# Connectors-SD.net
KiCad netlist of a schematic drawn in Altium Designer
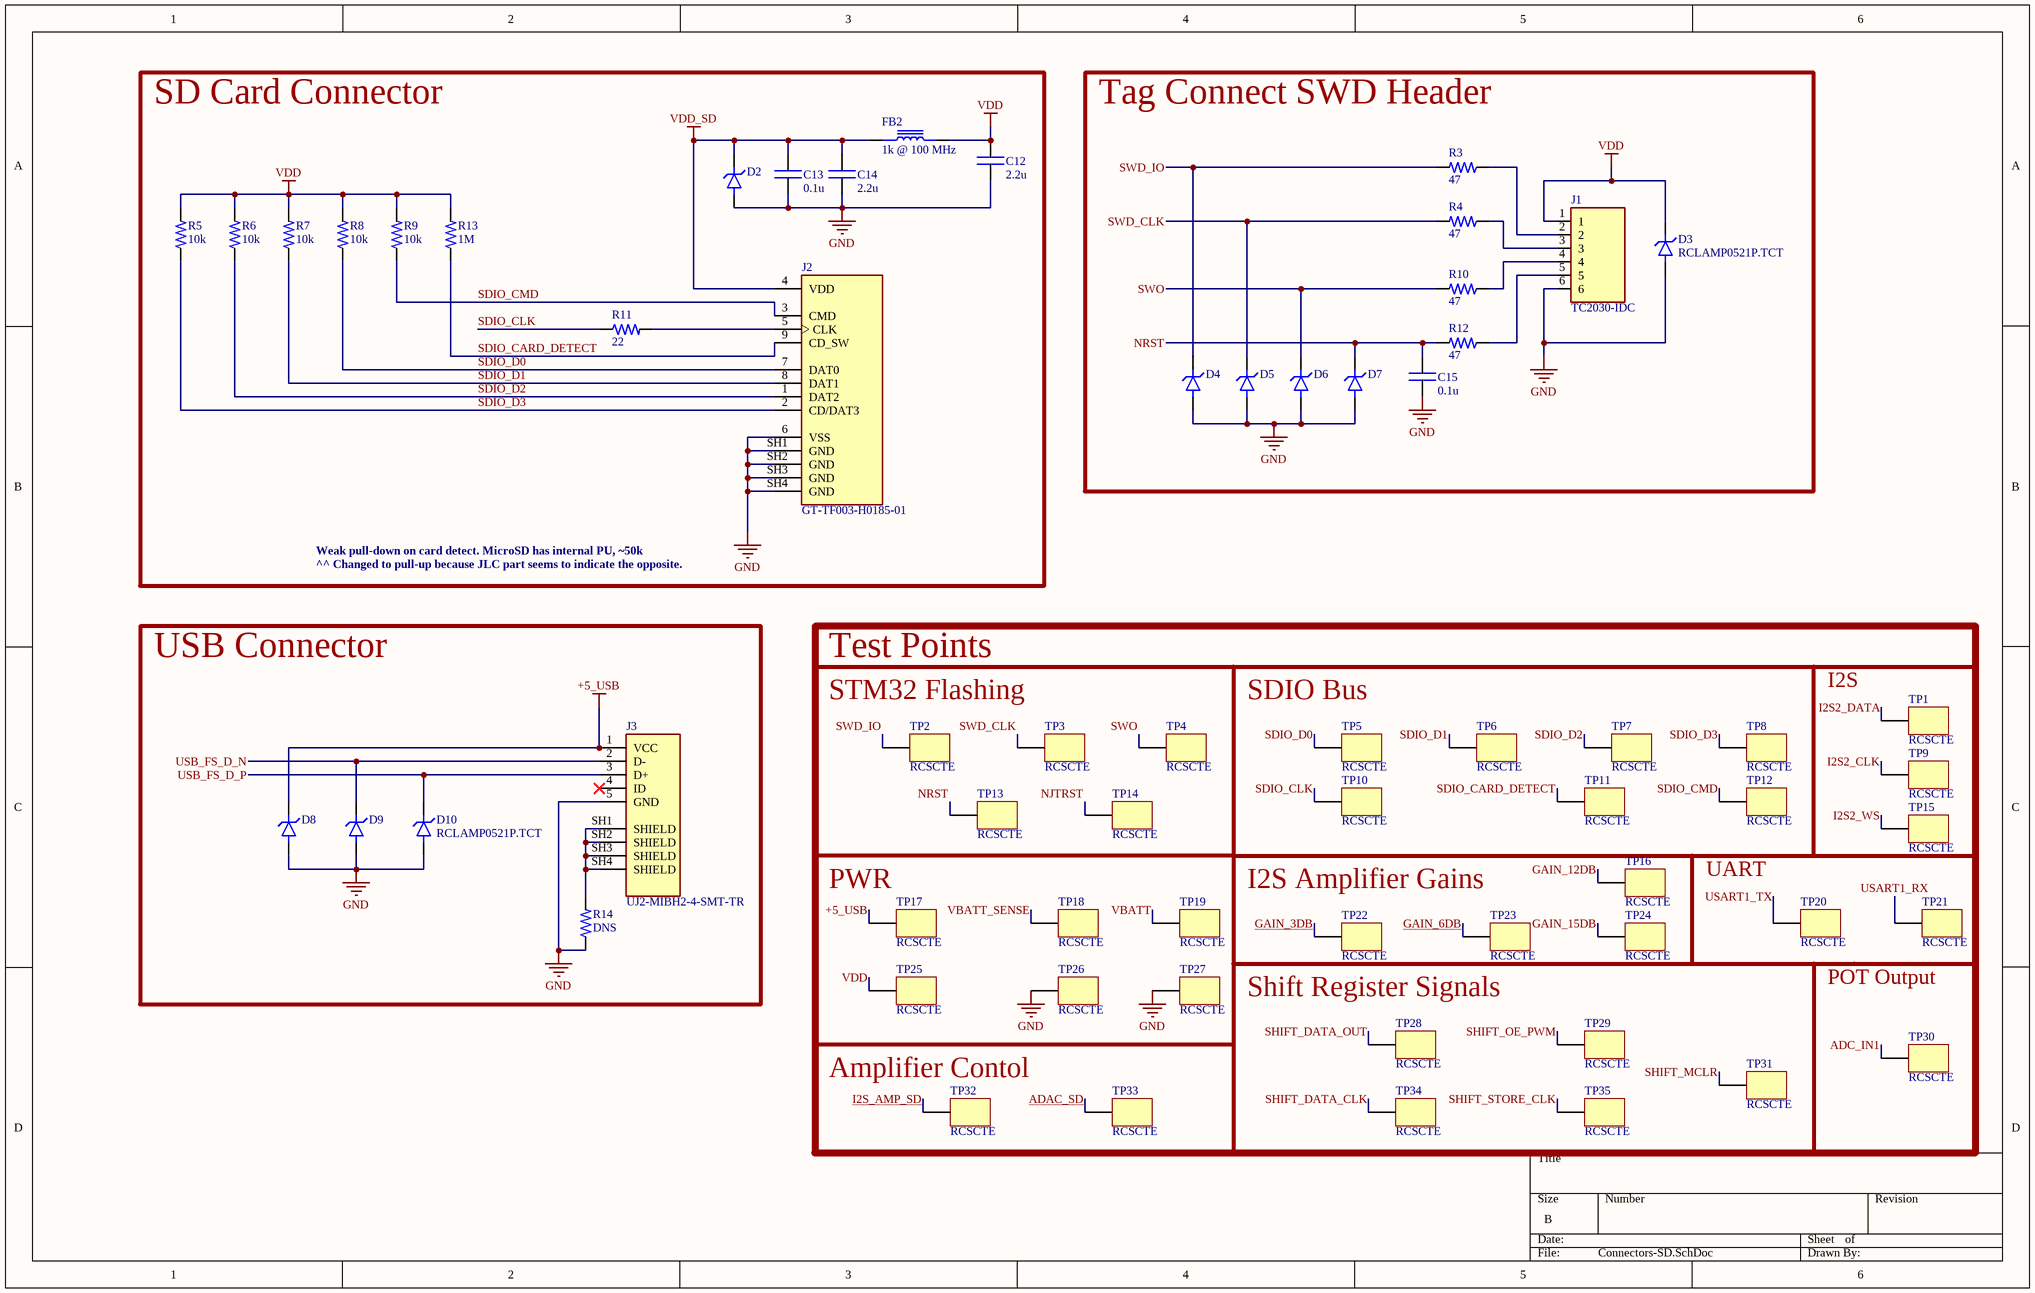
[diagram p0: Connectors-SD.SchDoc]

(export (version "E")
  (design (tool "Eeschema 10.0.6"))
  (components
    (comp (ref "C12")
      (value "2.2u")
      (footprint "Christmas-2023_Soundboard:0603-CAP")
      (description "Capaicitor")
      (fields (field (name "Comment") "CAP"))
      (libsource (lib "Christmas-2023_Soundboard") (part "CAP"))
    )
    (comp (ref "C13")
      (value "0.1u")
      (footprint "Christmas-2023_Soundboard:0603-CAP")
      (description "Capaicitor")
      (fields (field (name "Comment") "CAP"))
      (libsource (lib "Christmas-2023_Soundboard") (part "CAP"))
    )
    (comp (ref "C14")
      (value "2.2u")
      (footprint "Christmas-2023_Soundboard:0603-CAP")
      (description "Capaicitor")
      (fields (field (name "Comment") "CAP"))
      (libsource (lib "Christmas-2023_Soundboard") (part "CAP"))
    )
    (comp (ref "C15")
      (value "0.1u")
      (footprint "Christmas-2023_Soundboard:0603-CAP")
      (description "Capaicitor")
      (fields (field (name "Comment") "CAP"))
      (libsource (lib "Christmas-2023_Soundboard") (part "CAP"))
    )
    (comp (ref "D2")
      (value "RCLAMP0521P.TCT")
      (footprint "Christmas-2023_Soundboard:RCLAMP0521P.TCT")
      (description "25V Clamp 4A (8/20µs) Ipp Tvs Diode Surface Mount SLP1006P2")
      (fields (field (name "MFR") "Semtech Corporation"))
      (libsource (lib "Christmas-2023_Soundboard") (part "TVS DIODE"))
    )
    (comp (ref "D3")
      (value "RCLAMP0521P.TCT")
      (footprint "Christmas-2023_Soundboard:RCLAMP0521P.TCT")
      (description "25V Clamp 4A (8/20µs) Ipp Tvs Diode Surface Mount SLP1006P2")
      (fields (field (name "MFR") "Semtech Corporation"))
      (libsource (lib "Christmas-2023_Soundboard") (part "TVS DIODE"))
    )
    (comp (ref "D4")
      (value "RCLAMP0521P.TCT")
      (footprint "Christmas-2023_Soundboard:RCLAMP0521P.TCT")
      (description "25V Clamp 4A (8/20µs) Ipp Tvs Diode Surface Mount SLP1006P2")
      (fields (field (name "MFR") "Semtech Corporation"))
      (libsource (lib "Christmas-2023_Soundboard") (part "TVS DIODE"))
    )
    (comp (ref "D5")
      (value "RCLAMP0521P.TCT")
      (footprint "Christmas-2023_Soundboard:RCLAMP0521P.TCT")
      (description "25V Clamp 4A (8/20µs) Ipp Tvs Diode Surface Mount SLP1006P2")
      (fields (field (name "MFR") "Semtech Corporation"))
      (libsource (lib "Christmas-2023_Soundboard") (part "TVS DIODE"))
    )
    (comp (ref "D6")
      (value "RCLAMP0521P.TCT")
      (footprint "Christmas-2023_Soundboard:RCLAMP0521P.TCT")
      (description "25V Clamp 4A (8/20µs) Ipp Tvs Diode Surface Mount SLP1006P2")
      (fields (field (name "MFR") "Semtech Corporation"))
      (libsource (lib "Christmas-2023_Soundboard") (part "TVS DIODE"))
    )
    (comp (ref "D7")
      (value "RCLAMP0521P.TCT")
      (footprint "Christmas-2023_Soundboard:RCLAMP0521P.TCT")
      (description "25V Clamp 4A (8/20µs) Ipp Tvs Diode Surface Mount SLP1006P2")
      (fields (field (name "MFR") "Semtech Corporation"))
      (libsource (lib "Christmas-2023_Soundboard") (part "TVS DIODE"))
    )
    (comp (ref "D8")
      (value "RCLAMP0521P.TCT")
      (footprint "Christmas-2023_Soundboard:RCLAMP0521P.TCT")
      (description "25V Clamp 4A (8/20µs) Ipp Tvs Diode Surface Mount SLP1006P2")
      (fields (field (name "MFR") "Semtech Corporation"))
      (libsource (lib "Christmas-2023_Soundboard") (part "TVS DIODE"))
    )
    (comp (ref "D9")
      (value "RCLAMP0521P.TCT")
      (footprint "Christmas-2023_Soundboard:RCLAMP0521P.TCT")
      (description "25V Clamp 4A (8/20µs) Ipp Tvs Diode Surface Mount SLP1006P2")
      (fields (field (name "MFR") "Semtech Corporation"))
      (libsource (lib "Christmas-2023_Soundboard") (part "TVS DIODE"))
    )
    (comp (ref "D10")
      (value "RCLAMP0521P.TCT")
      (footprint "Christmas-2023_Soundboard:RCLAMP0521P.TCT")
      (description "25V Clamp 4A (8/20µs) Ipp Tvs Diode Surface Mount SLP1006P2")
      (fields (field (name "MFR") "Semtech Corporation"))
      (libsource (lib "Christmas-2023_Soundboard") (part "TVS DIODE"))
    )
    (comp (ref "FB2")
      (value "1k @ 100 MHz")
      (footprint "Christmas-2023_Soundboard:0603-FB")
      (fields (field (name "MFR") "TDK"))
      (libsource (lib "Christmas-2023_Soundboard") (part "FERRITE BEAD"))
    )
    (comp (ref "J1")
      (value "TC2030-IDC")
      (footprint "Christmas-2023_Soundboard:TAG CONNECT TC2030IDC - NO 3D MODEL")
      (description "\"Plug of Nails\" POGO Pin connector")
      (fields (field (name "MFR") "Tag-Connect"))
      (libsource (lib "Christmas-2023_Soundboard") (part "TAG CONNECT POGO HEADER"))
    )
    (comp (ref "J2")
      (value "GT-TF003-H0185-01")
      (footprint "Christmas-2023_Soundboard:GTTF003H018501")
      (fields (field (name "MFR") "G-Switch"))
      (libsource (lib "Christmas-2023_Soundboard") (part "SD-CONN-SMD_JLC"))
    )
    (comp (ref "J3")
      (value "UJ2-MIBH2-4-SMT-TR")
      (footprint "Christmas-2023_Soundboard:USB MICRO JLC")
      (description "Micro B, USB 2.0, 1.8 A, Right Angle, Surface Mount (SMT), USB Receptacle")
      (fields (field (name "MFR") "D-CHAIN"))
      (libsource (lib "Christmas-2023_Soundboard") (part "Micro USB Port"))
    )
    (comp (ref "R3")
      (value "47")
      (footprint "Christmas-2023_Soundboard:0603-RES")
      (description "Resistor")
      (fields (field (name "Comment") "RES"))
      (libsource (lib "Christmas-2023_Soundboard") (part "RES"))
    )
    (comp (ref "R4")
      (value "47")
      (footprint "Christmas-2023_Soundboard:0603-RES")
      (description "Resistor")
      (fields (field (name "Comment") "RES"))
      (libsource (lib "Christmas-2023_Soundboard") (part "RES"))
    )
    (comp (ref "R5")
      (value "10k")
      (footprint "Christmas-2023_Soundboard:0603-RES")
      (description "Resistor")
      (fields (field (name "Comment") "RES"))
      (libsource (lib "Christmas-2023_Soundboard") (part "RES"))
    )
    (comp (ref "R6")
      (value "10k")
      (footprint "Christmas-2023_Soundboard:0603-RES")
      (description "Resistor")
      (fields (field (name "Comment") "RES"))
      (libsource (lib "Christmas-2023_Soundboard") (part "RES"))
    )
    (comp (ref "R7")
      (value "10k")
      (footprint "Christmas-2023_Soundboard:0603-RES")
      (description "Resistor")
      (fields (field (name "Comment") "RES"))
      (libsource (lib "Christmas-2023_Soundboard") (part "RES"))
    )
    (comp (ref "R8")
      (value "10k")
      (footprint "Christmas-2023_Soundboard:0603-RES")
      (description "Resistor")
      (fields (field (name "Comment") "RES"))
      (libsource (lib "Christmas-2023_Soundboard") (part "RES"))
    )
    (comp (ref "R9")
      (value "10k")
      (footprint "Christmas-2023_Soundboard:0603-RES")
      (description "Resistor")
      (fields (field (name "Comment") "RES"))
      (libsource (lib "Christmas-2023_Soundboard") (part "RES"))
    )
    (comp (ref "R10")
      (value "47")
      (footprint "Christmas-2023_Soundboard:0603-RES")
      (description "Resistor")
      (fields (field (name "Comment") "RES"))
      (libsource (lib "Christmas-2023_Soundboard") (part "RES"))
    )
    (comp (ref "R11")
      (value "22")
      (footprint "Christmas-2023_Soundboard:0603-RES")
      (description "Resistor")
      (fields (field (name "Comment") "RES"))
      (libsource (lib "Christmas-2023_Soundboard") (part "RES"))
    )
    (comp (ref "R12")
      (value "47")
      (footprint "Christmas-2023_Soundboard:0603-RES")
      (description "Resistor")
      (fields (field (name "Comment") "RES"))
      (libsource (lib "Christmas-2023_Soundboard") (part "RES"))
    )
    (comp (ref "R13")
      (value "1M")
      (footprint "Christmas-2023_Soundboard:0603-RES")
      (description "Resistor")
      (fields (field (name "Comment") "RES"))
      (libsource (lib "Christmas-2023_Soundboard") (part "RES"))
    )
    (comp (ref "R14")
      (value "DNS")
      (footprint "Christmas-2023_Soundboard:0603-RES")
      (description "Resistor")
      (fields (field (name "Comment") "RES"))
      (libsource (lib "Christmas-2023_Soundboard") (part "RES"))
    )
    (comp (ref "TP1")
      (value "RCSCTE")
      (footprint "Christmas-2023_Soundboard:RCWCTE")
      (description "Test Point, Surface Mount")
      (fields (field (name "MFR") "KOA Speer Electronics, Inc."))
      (libsource (lib "Christmas-2023_Soundboard") (part "Test Point"))
    )
    (comp (ref "TP2")
      (value "RCSCTE")
      (footprint "Christmas-2023_Soundboard:RCWCTE")
      (description "Test Point, Surface Mount")
      (fields (field (name "MFR") "KOA Speer Electronics, Inc."))
      (libsource (lib "Christmas-2023_Soundboard") (part "Test Point"))
    )
    (comp (ref "TP3")
      (value "RCSCTE")
      (footprint "Christmas-2023_Soundboard:RCWCTE")
      (description "Test Point, Surface Mount")
      (fields (field (name "MFR") "KOA Speer Electronics, Inc."))
      (libsource (lib "Christmas-2023_Soundboard") (part "Test Point"))
    )
    (comp (ref "TP4")
      (value "RCSCTE")
      (footprint "Christmas-2023_Soundboard:RCWCTE")
      (description "Test Point, Surface Mount")
      (fields (field (name "MFR") "KOA Speer Electronics, Inc."))
      (libsource (lib "Christmas-2023_Soundboard") (part "Test Point"))
    )
    (comp (ref "TP5")
      (value "RCSCTE")
      (footprint "Christmas-2023_Soundboard:RCWCTE")
      (description "Test Point, Surface Mount")
      (fields (field (name "MFR") "KOA Speer Electronics, Inc."))
      (libsource (lib "Christmas-2023_Soundboard") (part "Test Point"))
    )
    (comp (ref "TP6")
      (value "RCSCTE")
      (footprint "Christmas-2023_Soundboard:RCWCTE")
      (description "Test Point, Surface Mount")
      (fields (field (name "MFR") "KOA Speer Electronics, Inc."))
      (libsource (lib "Christmas-2023_Soundboard") (part "Test Point"))
    )
    (comp (ref "TP7")
      (value "RCSCTE")
      (footprint "Christmas-2023_Soundboard:RCWCTE")
      (description "Test Point, Surface Mount")
      (fields (field (name "MFR") "KOA Speer Electronics, Inc."))
      (libsource (lib "Christmas-2023_Soundboard") (part "Test Point"))
    )
    (comp (ref "TP8")
      (value "RCSCTE")
      (footprint "Christmas-2023_Soundboard:RCWCTE")
      (description "Test Point, Surface Mount")
      (fields (field (name "MFR") "KOA Speer Electronics, Inc."))
      (libsource (lib "Christmas-2023_Soundboard") (part "Test Point"))
    )
    (comp (ref "TP9")
      (value "RCSCTE")
      (footprint "Christmas-2023_Soundboard:RCWCTE")
      (description "Test Point, Surface Mount")
      (fields (field (name "MFR") "KOA Speer Electronics, Inc."))
      (libsource (lib "Christmas-2023_Soundboard") (part "Test Point"))
    )
    (comp (ref "TP10")
      (value "RCSCTE")
      (footprint "Christmas-2023_Soundboard:RCWCTE")
      (description "Test Point, Surface Mount")
      (fields (field (name "MFR") "KOA Speer Electronics, Inc."))
      (libsource (lib "Christmas-2023_Soundboard") (part "Test Point"))
    )
    (comp (ref "TP11")
      (value "RCSCTE")
      (footprint "Christmas-2023_Soundboard:RCWCTE")
      (description "Test Point, Surface Mount")
      (fields (field (name "MFR") "KOA Speer Electronics, Inc."))
      (libsource (lib "Christmas-2023_Soundboard") (part "Test Point"))
    )
    (comp (ref "TP12")
      (value "RCSCTE")
      (footprint "Christmas-2023_Soundboard:RCWCTE")
      (description "Test Point, Surface Mount")
      (fields (field (name "MFR") "KOA Speer Electronics, Inc."))
      (libsource (lib "Christmas-2023_Soundboard") (part "Test Point"))
    )
    (comp (ref "TP13")
      (value "RCSCTE")
      (footprint "Christmas-2023_Soundboard:RCWCTE")
      (description "Test Point, Surface Mount")
      (fields (field (name "MFR") "KOA Speer Electronics, Inc."))
      (libsource (lib "Christmas-2023_Soundboard") (part "Test Point"))
    )
    (comp (ref "TP14")
      (value "RCSCTE")
      (footprint "Christmas-2023_Soundboard:RCWCTE")
      (description "Test Point, Surface Mount")
      (fields (field (name "MFR") "KOA Speer Electronics, Inc."))
      (libsource (lib "Christmas-2023_Soundboard") (part "Test Point"))
    )
    (comp (ref "TP15")
      (value "RCSCTE")
      (footprint "Christmas-2023_Soundboard:RCWCTE")
      (description "Test Point, Surface Mount")
      (fields (field (name "MFR") "KOA Speer Electronics, Inc."))
      (libsource (lib "Christmas-2023_Soundboard") (part "Test Point"))
    )
    (comp (ref "TP16")
      (value "RCSCTE")
      (footprint "Christmas-2023_Soundboard:RCWCTE")
      (description "Test Point, Surface Mount")
      (fields (field (name "MFR") "KOA Speer Electronics, Inc."))
      (libsource (lib "Christmas-2023_Soundboard") (part "Test Point"))
    )
    (comp (ref "TP17")
      (value "RCSCTE")
      (footprint "Christmas-2023_Soundboard:RCWCTE")
      (description "Test Point, Surface Mount")
      (fields (field (name "MFR") "KOA Speer Electronics, Inc."))
      (libsource (lib "Christmas-2023_Soundboard") (part "Test Point"))
    )
    (comp (ref "TP18")
      (value "RCSCTE")
      (footprint "Christmas-2023_Soundboard:RCWCTE")
      (description "Test Point, Surface Mount")
      (fields (field (name "MFR") "KOA Speer Electronics, Inc."))
      (libsource (lib "Christmas-2023_Soundboard") (part "Test Point"))
    )
    (comp (ref "TP19")
      (value "RCSCTE")
      (footprint "Christmas-2023_Soundboard:RCWCTE")
      (description "Test Point, Surface Mount")
      (fields (field (name "MFR") "KOA Speer Electronics, Inc."))
      (libsource (lib "Christmas-2023_Soundboard") (part "Test Point"))
    )
    (comp (ref "TP20")
      (value "RCSCTE")
      (footprint "Christmas-2023_Soundboard:RCWCTE")
      (description "Test Point, Surface Mount")
      (fields (field (name "MFR") "KOA Speer Electronics, Inc."))
      (libsource (lib "Christmas-2023_Soundboard") (part "Test Point"))
    )
    (comp (ref "TP21")
      (value "RCSCTE")
      (footprint "Christmas-2023_Soundboard:RCWCTE")
      (description "Test Point, Surface Mount")
      (fields (field (name "MFR") "KOA Speer Electronics, Inc."))
      (libsource (lib "Christmas-2023_Soundboard") (part "Test Point"))
    )
    (comp (ref "TP22")
      (value "RCSCTE")
      (footprint "Christmas-2023_Soundboard:RCWCTE")
      (description "Test Point, Surface Mount")
      (fields (field (name "MFR") "KOA Speer Electronics, Inc."))
      (libsource (lib "Christmas-2023_Soundboard") (part "Test Point"))
    )
    (comp (ref "TP23")
      (value "RCSCTE")
      (footprint "Christmas-2023_Soundboard:RCWCTE")
      (description "Test Point, Surface Mount")
      (fields (field (name "MFR") "KOA Speer Electronics, Inc."))
      (libsource (lib "Christmas-2023_Soundboard") (part "Test Point"))
    )
    (comp (ref "TP24")
      (value "RCSCTE")
      (footprint "Christmas-2023_Soundboard:RCWCTE")
      (description "Test Point, Surface Mount")
      (fields (field (name "MFR") "KOA Speer Electronics, Inc."))
      (libsource (lib "Christmas-2023_Soundboard") (part "Test Point"))
    )
    (comp (ref "TP25")
      (value "RCSCTE")
      (footprint "Christmas-2023_Soundboard:RCWCTE")
      (description "Test Point, Surface Mount")
      (fields (field (name "MFR") "KOA Speer Electronics, Inc."))
      (libsource (lib "Christmas-2023_Soundboard") (part "Test Point"))
    )
    (comp (ref "TP26")
      (value "RCSCTE")
      (footprint "Christmas-2023_Soundboard:RCWCTE")
      (description "Test Point, Surface Mount")
      (fields (field (name "MFR") "KOA Speer Electronics, Inc."))
      (libsource (lib "Christmas-2023_Soundboard") (part "Test Point"))
    )
    (comp (ref "TP27")
      (value "RCSCTE")
      (footprint "Christmas-2023_Soundboard:RCWCTE")
      (description "Test Point, Surface Mount")
      (fields (field (name "MFR") "KOA Speer Electronics, Inc."))
      (libsource (lib "Christmas-2023_Soundboard") (part "Test Point"))
    )
    (comp (ref "TP28")
      (value "RCSCTE")
      (footprint "Christmas-2023_Soundboard:RCWCTE")
      (description "Test Point, Surface Mount")
      (fields (field (name "MFR") "KOA Speer Electronics, Inc."))
      (libsource (lib "Christmas-2023_Soundboard") (part "Test Point"))
    )
    (comp (ref "TP29")
      (value "RCSCTE")
      (footprint "Christmas-2023_Soundboard:RCWCTE")
      (description "Test Point, Surface Mount")
      (fields (field (name "MFR") "KOA Speer Electronics, Inc."))
      (libsource (lib "Christmas-2023_Soundboard") (part "Test Point"))
    )
    (comp (ref "TP30")
      (value "RCSCTE")
      (footprint "Christmas-2023_Soundboard:RCWCTE")
      (description "Test Point, Surface Mount")
      (fields (field (name "MFR") "KOA Speer Electronics, Inc."))
      (libsource (lib "Christmas-2023_Soundboard") (part "Test Point"))
    )
    (comp (ref "TP31")
      (value "RCSCTE")
      (footprint "Christmas-2023_Soundboard:RCWCTE")
      (description "Test Point, Surface Mount")
      (fields (field (name "MFR") "KOA Speer Electronics, Inc."))
      (libsource (lib "Christmas-2023_Soundboard") (part "Test Point"))
    )
    (comp (ref "TP32")
      (value "RCSCTE")
      (footprint "Christmas-2023_Soundboard:RCWCTE")
      (description "Test Point, Surface Mount")
      (fields (field (name "MFR") "KOA Speer Electronics, Inc."))
      (libsource (lib "Christmas-2023_Soundboard") (part "Test Point"))
    )
    (comp (ref "TP33")
      (value "RCSCTE")
      (footprint "Christmas-2023_Soundboard:RCWCTE")
      (description "Test Point, Surface Mount")
      (fields (field (name "MFR") "KOA Speer Electronics, Inc."))
      (libsource (lib "Christmas-2023_Soundboard") (part "Test Point"))
    )
    (comp (ref "TP34")
      (value "RCSCTE")
      (footprint "Christmas-2023_Soundboard:RCWCTE")
      (description "Test Point, Surface Mount")
      (fields (field (name "MFR") "KOA Speer Electronics, Inc."))
      (libsource (lib "Christmas-2023_Soundboard") (part "Test Point"))
    )
    (comp (ref "TP35")
      (value "RCSCTE")
      (footprint "Christmas-2023_Soundboard:RCWCTE")
      (description "Test Point, Surface Mount")
      (fields (field (name "MFR") "KOA Speer Electronics, Inc."))
      (libsource (lib "Christmas-2023_Soundboard") (part "Test Point"))
    )
  )
  (nets
    (net (code "1") (name "+5_USB") (class "Default")
      (node (ref "D8") (pin "K") (pinfunction "K_K") (pintype "passive"))
      (node (ref "J3") (pin "1") (pinfunction "VCC_1") (pintype "passive"))
      (node (ref "TP17") (pin "1") (pinfunction "0_1") (pintype "passive"))
    )
    (net (code "2") (name "/ADAC_SD") (class "Default")
      (node (ref "TP33") (pin "1") (pinfunction "0_1") (pintype "passive"))
    )
    (net (code "3") (name "/ADC_IN1") (class "Default")
      (node (ref "TP30") (pin "1") (pinfunction "0_1") (pintype "passive"))
    )
    (net (code "4") (name "/GAIN_3DB") (class "Default")
      (node (ref "TP22") (pin "1") (pinfunction "0_1") (pintype "passive"))
    )
    (net (code "5") (name "/GAIN_6DB") (class "Default")
      (node (ref "TP23") (pin "1") (pinfunction "0_1") (pintype "passive"))
    )
    (net (code "6") (name "/GAIN_12DB") (class "Default")
      (node (ref "TP16") (pin "1") (pinfunction "0_1") (pintype "passive"))
    )
    (net (code "7") (name "/GAIN_15DB") (class "Default")
      (node (ref "TP24") (pin "1") (pinfunction "0_1") (pintype "passive"))
    )
    (net (code "8") (name "/I2S2_CLK") (class "Default")
      (node (ref "TP9") (pin "1") (pinfunction "0_1") (pintype "passive"))
    )
    (net (code "9") (name "/I2S2_DATA") (class "Default")
      (node (ref "TP1") (pin "1") (pinfunction "0_1") (pintype "passive"))
    )
    (net (code "10") (name "/I2S2_WS") (class "Default")
      (node (ref "TP15") (pin "1") (pinfunction "0_1") (pintype "passive"))
    )
    (net (code "11") (name "/I2S_AMP_SD") (class "Default")
      (node (ref "TP32") (pin "1") (pinfunction "0_1") (pintype "passive"))
    )
    (net (code "12") (name "/NJTRST") (class "Default")
      (node (ref "TP14") (pin "1") (pinfunction "0_1") (pintype "passive"))
    )
    (net (code "13") (name "/NRST") (class "Default")
      (node (ref "C15") (pin "2") (pinfunction "2_2") (pintype "passive"))
      (node (ref "D7") (pin "K") (pinfunction "K_K") (pintype "passive"))
      (node (ref "R12") (pin "2") (pinfunction "2_2") (pintype "passive"))
      (node (ref "TP13") (pin "1") (pinfunction "0_1") (pintype "passive"))
    )
    (net (code "14") (name "/SDIO_CARD_DETECT") (class "Default")
      (node (ref "J2") (pin "9") (pinfunction "CD_SW_9") (pintype "passive"))
      (node (ref "R13") (pin "1") (pinfunction "1_1") (pintype "passive"))
      (node (ref "TP11") (pin "1") (pinfunction "0_1") (pintype "passive"))
    )
    (net (code "15") (name "/SDIO_CLK") (class "Default")
      (node (ref "R11") (pin "1") (pinfunction "1_1") (pintype "passive"))
      (node (ref "TP10") (pin "1") (pinfunction "0_1") (pintype "passive"))
    )
    (net (code "16") (name "/SDIO_CMD") (class "Default")
      (node (ref "J2") (pin "3") (pinfunction "CMD_3") (pintype "passive"))
      (node (ref "R9") (pin "1") (pinfunction "1_1") (pintype "passive"))
      (node (ref "TP12") (pin "1") (pinfunction "0_1") (pintype "passive"))
    )
    (net (code "17") (name "/SDIO_D0") (class "Default")
      (node (ref "J2") (pin "7") (pinfunction "DAT0_7") (pintype "passive"))
      (node (ref "R8") (pin "1") (pinfunction "1_1") (pintype "passive"))
      (node (ref "TP5") (pin "1") (pinfunction "0_1") (pintype "passive"))
    )
    (net (code "18") (name "/SDIO_D1") (class "Default")
      (node (ref "J2") (pin "8") (pinfunction "DAT1_8") (pintype "passive"))
      (node (ref "R7") (pin "1") (pinfunction "1_1") (pintype "passive"))
      (node (ref "TP6") (pin "1") (pinfunction "0_1") (pintype "passive"))
    )
    (net (code "19") (name "/SDIO_D2") (class "Default")
      (node (ref "J2") (pin "1") (pinfunction "DAT2_1") (pintype "passive"))
      (node (ref "R6") (pin "1") (pinfunction "1_1") (pintype "passive"))
      (node (ref "TP7") (pin "1") (pinfunction "0_1") (pintype "passive"))
    )
    (net (code "20") (name "/SDIO_D3") (class "Default")
      (node (ref "J2") (pin "2") (pinfunction "CD/DAT3_2") (pintype "passive"))
      (node (ref "R5") (pin "1") (pinfunction "1_1") (pintype "passive"))
      (node (ref "TP8") (pin "1") (pinfunction "0_1") (pintype "passive"))
    )
    (net (code "21") (name "/SHIFT_DATA_CLK") (class "Default")
      (node (ref "TP34") (pin "1") (pinfunction "0_1") (pintype "passive"))
    )
    (net (code "22") (name "/SHIFT_DATA_OUT") (class "Default")
      (node (ref "TP28") (pin "1") (pinfunction "0_1") (pintype "passive"))
    )
    (net (code "23") (name "/SHIFT_MCLR") (class "Default")
      (node (ref "TP31") (pin "1") (pinfunction "0_1") (pintype "passive"))
    )
    (net (code "24") (name "/SHIFT_OE_PWM") (class "Default")
      (node (ref "TP29") (pin "1") (pinfunction "0_1") (pintype "passive"))
    )
    (net (code "25") (name "/SHIFT_STORE_CLK") (class "Default")
      (node (ref "TP35") (pin "1") (pinfunction "0_1") (pintype "passive"))
    )
    (net (code "26") (name "/SWD_CLK") (class "Default")
      (node (ref "D5") (pin "K") (pinfunction "K_K") (pintype "passive"))
      (node (ref "R4") (pin "2") (pinfunction "2_2") (pintype "passive"))
      (node (ref "TP3") (pin "1") (pinfunction "0_1") (pintype "passive"))
    )
    (net (code "27") (name "/SWD_IO") (class "Default")
      (node (ref "D4") (pin "K") (pinfunction "K_K") (pintype "passive"))
      (node (ref "R3") (pin "2") (pinfunction "2_2") (pintype "passive"))
      (node (ref "TP2") (pin "1") (pinfunction "0_1") (pintype "passive"))
    )
    (net (code "28") (name "/SWO") (class "Default")
      (node (ref "D6") (pin "K") (pinfunction "K_K") (pintype "passive"))
      (node (ref "R10") (pin "2") (pinfunction "2_2") (pintype "passive"))
      (node (ref "TP4") (pin "1") (pinfunction "0_1") (pintype "passive"))
    )
    (net (code "29") (name "/USART1_RX") (class "Default")
      (node (ref "TP21") (pin "1") (pinfunction "0_1") (pintype "passive"))
    )
    (net (code "30") (name "/USART1_TX") (class "Default")
      (node (ref "TP20") (pin "1") (pinfunction "0_1") (pintype "passive"))
    )
    (net (code "31") (name "/USB_FS_D_N") (class "Default")
      (node (ref "D9") (pin "K") (pinfunction "K_K") (pintype "passive"))
      (node (ref "J3") (pin "2") (pinfunction "D-_2") (pintype "passive"))
    )
    (net (code "32") (name "/USB_FS_D_P") (class "Default")
      (node (ref "D10") (pin "K") (pinfunction "K_K") (pintype "passive"))
      (node (ref "J3") (pin "3") (pinfunction "D+_3") (pintype "passive"))
    )
    (net (code "33") (name "/VBATT") (class "Default")
      (node (ref "TP19") (pin "1") (pinfunction "0_1") (pintype "passive"))
    )
    (net (code "34") (name "/VBATT_SENSE") (class "Default")
      (node (ref "TP18") (pin "1") (pinfunction "0_1") (pintype "passive"))
    )
    (net (code "35") (name "GND") (class "Default")
      (node (ref "C12") (pin "1") (pinfunction "1_1") (pintype "passive"))
      (node (ref "C13") (pin "1") (pinfunction "1_1") (pintype "passive"))
      (node (ref "C14") (pin "1") (pinfunction "1_1") (pintype "passive"))
      (node (ref "C15") (pin "1") (pinfunction "1_1") (pintype "passive"))
      (node (ref "D10") (pin "A") (pinfunction "A_A") (pintype "passive"))
      (node (ref "D2") (pin "A") (pinfunction "A_A") (pintype "passive"))
      (node (ref "D3") (pin "A") (pinfunction "A_A") (pintype "passive"))
      (node (ref "D4") (pin "A") (pinfunction "A_A") (pintype "passive"))
      (node (ref "D5") (pin "A") (pinfunction "A_A") (pintype "passive"))
      (node (ref "D6") (pin "A") (pinfunction "A_A") (pintype "passive"))
      (node (ref "D7") (pin "A") (pinfunction "A_A") (pintype "passive"))
      (node (ref "D8") (pin "A") (pinfunction "A_A") (pintype "passive"))
      (node (ref "D9") (pin "A") (pinfunction "A_A") (pintype "passive"))
      (node (ref "J1") (pin "6") (pinfunction "6_6") (pintype "passive"))
      (node (ref "J2") (pin "6") (pinfunction "VSS_6") (pintype "passive"))
      (node (ref "J2") (pin "SH1") (pinfunction "GND_SH1") (pintype "passive"))
      (node (ref "J2") (pin "SH2") (pinfunction "GND_SH2") (pintype "passive"))
      (node (ref "J2") (pin "SH3") (pinfunction "GND_SH3") (pintype "passive"))
      (node (ref "J2") (pin "SH4") (pinfunction "GND_SH4") (pintype "passive"))
      (node (ref "J3") (pin "5") (pinfunction "GND_5") (pintype "passive"))
      (node (ref "R14") (pin "1") (pinfunction "1_1") (pintype "passive"))
      (node (ref "TP26") (pin "1") (pinfunction "0_1") (pintype "passive"))
      (node (ref "TP27") (pin "1") (pinfunction "0_1") (pintype "passive"))
    )
    (net (code "36") (name "Net-(J1-Pad2)") (class "Default")
      (node (ref "J1") (pin "2") (pinfunction "2_2") (pintype "passive"))
      (node (ref "R3") (pin "1") (pinfunction "1_1") (pintype "passive"))
    )
    (net (code "37") (name "Net-(J1-Pad3)") (class "Default")
      (node (ref "J1") (pin "3") (pinfunction "3_3") (pintype "passive"))
      (node (ref "R4") (pin "1") (pinfunction "1_1") (pintype "passive"))
    )
    (net (code "38") (name "Net-(J1-Pad4)") (class "Default")
      (node (ref "J1") (pin "4") (pinfunction "4_4") (pintype "passive"))
      (node (ref "R10") (pin "1") (pinfunction "1_1") (pintype "passive"))
    )
    (net (code "39") (name "Net-(J1-Pad5)") (class "Default")
      (node (ref "J1") (pin "5") (pinfunction "5_5") (pintype "passive"))
      (node (ref "R12") (pin "1") (pinfunction "1_1") (pintype "passive"))
    )
    (net (code "40") (name "Net-(J2-CLK)") (class "Default")
      (node (ref "J2") (pin "5") (pinfunction "CLK_5") (pintype "passive"))
      (node (ref "R11") (pin "2") (pinfunction "2_2") (pintype "passive"))
    )
    (net (code "41") (name "Net-(J3-SHIELD-PadSH1)") (class "Default")
      (node (ref "J3") (pin "SH1") (pinfunction "SHIELD_SH1") (pintype "passive"))
      (node (ref "J3") (pin "SH2") (pinfunction "SHIELD_SH2") (pintype "passive"))
      (node (ref "J3") (pin "SH3") (pinfunction "SHIELD_SH3") (pintype "passive"))
      (node (ref "J3") (pin "SH4") (pinfunction "SHIELD_SH4") (pintype "passive"))
      (node (ref "R14") (pin "2") (pinfunction "2_2") (pintype "passive"))
    )
    (net (code "42") (name "VDD") (class "Default")
      (node (ref "C12") (pin "2") (pinfunction "2_2") (pintype "passive"))
      (node (ref "D3") (pin "K") (pinfunction "K_K") (pintype "passive"))
      (node (ref "FB2") (pin "2") (pinfunction "2_2") (pintype "passive"))
      (node (ref "J1") (pin "1") (pinfunction "1_1") (pintype "passive"))
      (node (ref "R13") (pin "2") (pinfunction "2_2") (pintype "passive"))
      (node (ref "R5") (pin "2") (pinfunction "2_2") (pintype "passive"))
      (node (ref "R6") (pin "2") (pinfunction "2_2") (pintype "passive"))
      (node (ref "R7") (pin "2") (pinfunction "2_2") (pintype "passive"))
      (node (ref "R8") (pin "2") (pinfunction "2_2") (pintype "passive"))
      (node (ref "R9") (pin "2") (pinfunction "2_2") (pintype "passive"))
      (node (ref "TP25") (pin "1") (pinfunction "0_1") (pintype "passive"))
    )
    (net (code "43") (name "VDD_SD") (class "Default")
      (node (ref "C13") (pin "2") (pinfunction "2_2") (pintype "passive"))
      (node (ref "C14") (pin "2") (pinfunction "2_2") (pintype "passive"))
      (node (ref "D2") (pin "K") (pinfunction "K_K") (pintype "passive"))
      (node (ref "FB2") (pin "1") (pinfunction "1_1") (pintype "passive"))
      (node (ref "J2") (pin "4") (pinfunction "VDD_4") (pintype "passive"))
    )
    (net (code "44") (name "unconnected-(J3-ID-Pad4)") (class "Default")
      (node (ref "J3") (pin "4") (pinfunction "ID_4") (pintype "passive+no_connect"))
    )
  )
)
